# k1.net
KiCad netlist of a schematic drawn in EAGLE
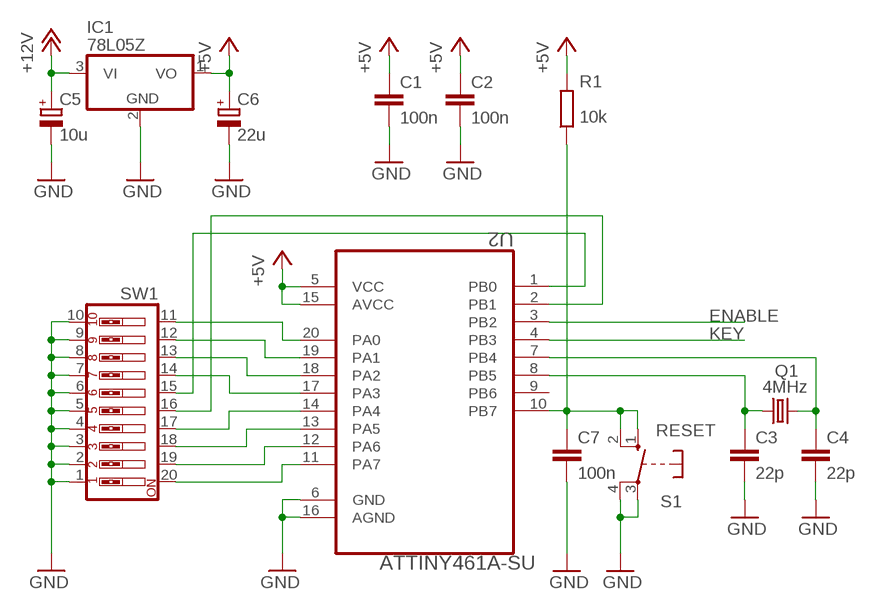
[diagram p0: schematic, sheet 1]

(export (version "E")
  (design (tool "Eeschema 10.0.6"))
  (components
    (comp (ref "C1")
      (value "100n")
      (footprint "eagle-import:C025-024X044")
      (libsource (lib "eagle-import") (part "C-EU025-024X044"))
    )
    (comp (ref "C2")
      (value "100n")
      (footprint "eagle-import:C025-024X044")
      (libsource (lib "eagle-import") (part "C-EU025-024X044"))
    )
    (comp (ref "C3")
      (value "22p")
      (footprint "eagle-import:C025-024X044")
      (libsource (lib "eagle-import") (part "C-EU025-024X044"))
    )
    (comp (ref "C4")
      (value "22p")
      (footprint "eagle-import:C025-024X044")
      (libsource (lib "eagle-import") (part "C-EU025-024X044"))
    )
    (comp (ref "C5")
      (value "10u")
      (footprint "eagle-import:E2,5-5")
      (libsource (lib "eagle-import") (part "CPOL-EUE2.5-5"))
    )
    (comp (ref "C6")
      (value "22u")
      (footprint "eagle-import:E2,5-5")
      (libsource (lib "eagle-import") (part "CPOL-EUE2.5-5"))
    )
    (comp (ref "C7")
      (value "100n")
      (footprint "eagle-import:C025-024X044")
      (libsource (lib "eagle-import") (part "C-EU025-024X044"))
    )
    (comp (ref "IC1")
      (value "78L05Z")
      (footprint "eagle-import:TO92")
      (libsource (lib "eagle-import") (part "78ZL05"))
    )
    (comp (ref "Q1")
      (value "4MHz")
      (footprint "eagle-import:HC49_S")
      (libsource (lib "eagle-import") (part "CRYSTALHC49S"))
    )
    (comp (ref "R1")
      (value "10k")
      (footprint "eagle-import:0207_10")
      (libsource (lib "eagle-import") (part "R-EU_0207/10"))
    )
    (comp (ref "S1")
      (value "RESET")
      (footprint "eagle-import:RACON12")
      (libsource (lib "eagle-import") (part "RACON12"))
    )
    (comp (ref "SW1")
      (value "SW_DIP-10")
      (footprint "eagle-import:EDG-10")
      (libsource (lib "eagle-import") (part "SW_DIP-10"))
    )
    (comp (ref "U2")
      (value "ATTINY461A-SU")
      (footprint "eagle-import:SOIC127P1032X265-20N")
      (libsource (lib "eagle-import") (part "ATTINY461A-SU"))
    )
  )
  (nets
    (net (code "1") (name "+5V") (class "Default")
      (node (ref "C1") (pin "1") (pinfunction "1_1") (pintype "passive"))
      (node (ref "C2") (pin "1") (pinfunction "1_1") (pintype "passive"))
      (node (ref "C6") (pin "+") (pinfunction "+_+") (pintype "passive"))
      (node (ref "IC1") (pin "1") (pinfunction "VO_1") (pintype "passive"))
      (node (ref "R1") (pin "2") (pinfunction "2_2") (pintype "passive"))
      (node (ref "U2") (pin "15") (pinfunction "AVCC_15") (pintype "power_in"))
      (node (ref "U2") (pin "5") (pinfunction "VCC_5") (pintype "power_in"))
    )
    (net (code "2") (name "+12V") (class "Default")
      (node (ref "C5") (pin "+") (pinfunction "+_+") (pintype "passive"))
      (node (ref "IC1") (pin "3") (pinfunction "VI_3") (pintype "input"))
    )
    (net (code "3") (name "/ENABLE") (class "Default")
      (node (ref "U2") (pin "3") (pinfunction "PB2_3") (pintype "bidirectional"))
    )
    (net (code "4") (name "/KEY") (class "Default")
      (node (ref "U2") (pin "4") (pinfunction "PB3_4") (pintype "bidirectional"))
    )
    (net (code "5") (name "GND") (class "Default")
      (node (ref "C1") (pin "2") (pinfunction "2_2") (pintype "passive"))
      (node (ref "C2") (pin "2") (pinfunction "2_2") (pintype "passive"))
      (node (ref "C3") (pin "2") (pinfunction "2_2") (pintype "passive"))
      (node (ref "C4") (pin "2") (pinfunction "2_2") (pintype "passive"))
      (node (ref "C5") (pin "-") (pinfunction "-_-") (pintype "passive"))
      (node (ref "C6") (pin "-") (pinfunction "-_-") (pintype "passive"))
      (node (ref "C7") (pin "2") (pinfunction "2_2") (pintype "passive"))
      (node (ref "IC1") (pin "2") (pinfunction "GND_2") (pintype "passive"))
      (node (ref "S1") (pin "3") (pinfunction "P_3") (pintype "passive"))
      (node (ref "S1") (pin "4") (pinfunction "P_4") (pintype "passive"))
      (node (ref "SW1") (pin "1") (pinfunction "1_1") (pintype "passive"))
      (node (ref "SW1") (pin "10") (pinfunction "10_10") (pintype "passive"))
      (node (ref "SW1") (pin "2") (pinfunction "2_2") (pintype "passive"))
      (node (ref "SW1") (pin "3") (pinfunction "3_3") (pintype "passive"))
      (node (ref "SW1") (pin "4") (pinfunction "4_4") (pintype "passive"))
      (node (ref "SW1") (pin "5") (pinfunction "5_5") (pintype "passive"))
      (node (ref "SW1") (pin "6") (pinfunction "6_6") (pintype "passive"))
      (node (ref "SW1") (pin "7") (pinfunction "7_7") (pintype "passive"))
      (node (ref "SW1") (pin "8") (pinfunction "8_8") (pintype "passive"))
      (node (ref "SW1") (pin "9") (pinfunction "9_9") (pintype "passive"))
      (node (ref "U2") (pin "16") (pinfunction "AGND_16") (pintype "passive"))
      (node (ref "U2") (pin "6") (pinfunction "GND_6") (pintype "passive"))
    )
    (net (code "6") (name "Net-(U2-PA0)") (class "Default")
      (node (ref "SW1") (pin "11") (pinfunction "11_11") (pintype "passive"))
      (node (ref "U2") (pin "20") (pinfunction "PA0_20") (pintype "bidirectional"))
    )
    (net (code "7") (name "Net-(U2-PA1)") (class "Default")
      (node (ref "SW1") (pin "12") (pinfunction "12_12") (pintype "passive"))
      (node (ref "U2") (pin "19") (pinfunction "PA1_19") (pintype "bidirectional"))
    )
    (net (code "8") (name "Net-(U2-PA2)") (class "Default")
      (node (ref "SW1") (pin "13") (pinfunction "13_13") (pintype "passive"))
      (node (ref "U2") (pin "18") (pinfunction "PA2_18") (pintype "bidirectional"))
    )
    (net (code "9") (name "Net-(U2-PA3)") (class "Default")
      (node (ref "SW1") (pin "14") (pinfunction "14_14") (pintype "passive"))
      (node (ref "U2") (pin "17") (pinfunction "PA3_17") (pintype "bidirectional"))
    )
    (net (code "10") (name "Net-(U2-PA4)") (class "Default")
      (node (ref "SW1") (pin "17") (pinfunction "17_17") (pintype "passive"))
      (node (ref "U2") (pin "14") (pinfunction "PA4_14") (pintype "bidirectional"))
    )
    (net (code "11") (name "Net-(U2-PA5)") (class "Default")
      (node (ref "SW1") (pin "18") (pinfunction "18_18") (pintype "passive"))
      (node (ref "U2") (pin "13") (pinfunction "PA5_13") (pintype "bidirectional"))
    )
    (net (code "12") (name "Net-(U2-PA6)") (class "Default")
      (node (ref "SW1") (pin "19") (pinfunction "19_19") (pintype "passive"))
      (node (ref "U2") (pin "12") (pinfunction "PA6_12") (pintype "bidirectional"))
    )
    (net (code "13") (name "Net-(U2-PA7)") (class "Default")
      (node (ref "SW1") (pin "20") (pinfunction "20_20") (pintype "passive"))
      (node (ref "U2") (pin "11") (pinfunction "PA7_11") (pintype "bidirectional"))
    )
    (net (code "14") (name "Net-(U2-PB0)") (class "Default")
      (node (ref "SW1") (pin "15") (pinfunction "15_15") (pintype "passive"))
      (node (ref "U2") (pin "1") (pinfunction "PB0_1") (pintype "bidirectional"))
    )
    (net (code "15") (name "Net-(U2-PB1)") (class "Default")
      (node (ref "SW1") (pin "16") (pinfunction "16_16") (pintype "passive"))
      (node (ref "U2") (pin "2") (pinfunction "PB1_2") (pintype "bidirectional"))
    )
    (net (code "16") (name "Net-(U2-PB4)") (class "Default")
      (node (ref "C4") (pin "1") (pinfunction "1_1") (pintype "passive"))
      (node (ref "Q1") (pin "2") (pinfunction "2_2") (pintype "passive"))
      (node (ref "U2") (pin "7") (pinfunction "PB4_7") (pintype "bidirectional"))
    )
    (net (code "17") (name "Net-(U2-PB5)") (class "Default")
      (node (ref "C3") (pin "1") (pinfunction "1_1") (pintype "passive"))
      (node (ref "Q1") (pin "1") (pinfunction "1_1") (pintype "passive"))
      (node (ref "U2") (pin "8") (pinfunction "PB5_8") (pintype "bidirectional"))
    )
    (net (code "18") (name "Net-(U2-PB7)") (class "Default")
      (node (ref "C7") (pin "1") (pinfunction "1_1") (pintype "passive"))
      (node (ref "R1") (pin "1") (pinfunction "1_1") (pintype "passive"))
      (node (ref "S1") (pin "1") (pinfunction "S_1") (pintype "passive"))
      (node (ref "S1") (pin "2") (pinfunction "S_2") (pintype "passive"))
      (node (ref "U2") (pin "10") (pinfunction "PB7_10") (pintype "bidirectional"))
    )
    (net (code "19") (name "unconnected-(U2-PB6-Pad9)") (class "Default")
      (node (ref "U2") (pin "9") (pinfunction "PB6_9") (pintype "bidirectional"))
    )
  )
)
